# 7688A.net
KiCad netlist of a schematic drawn in Altium Designer
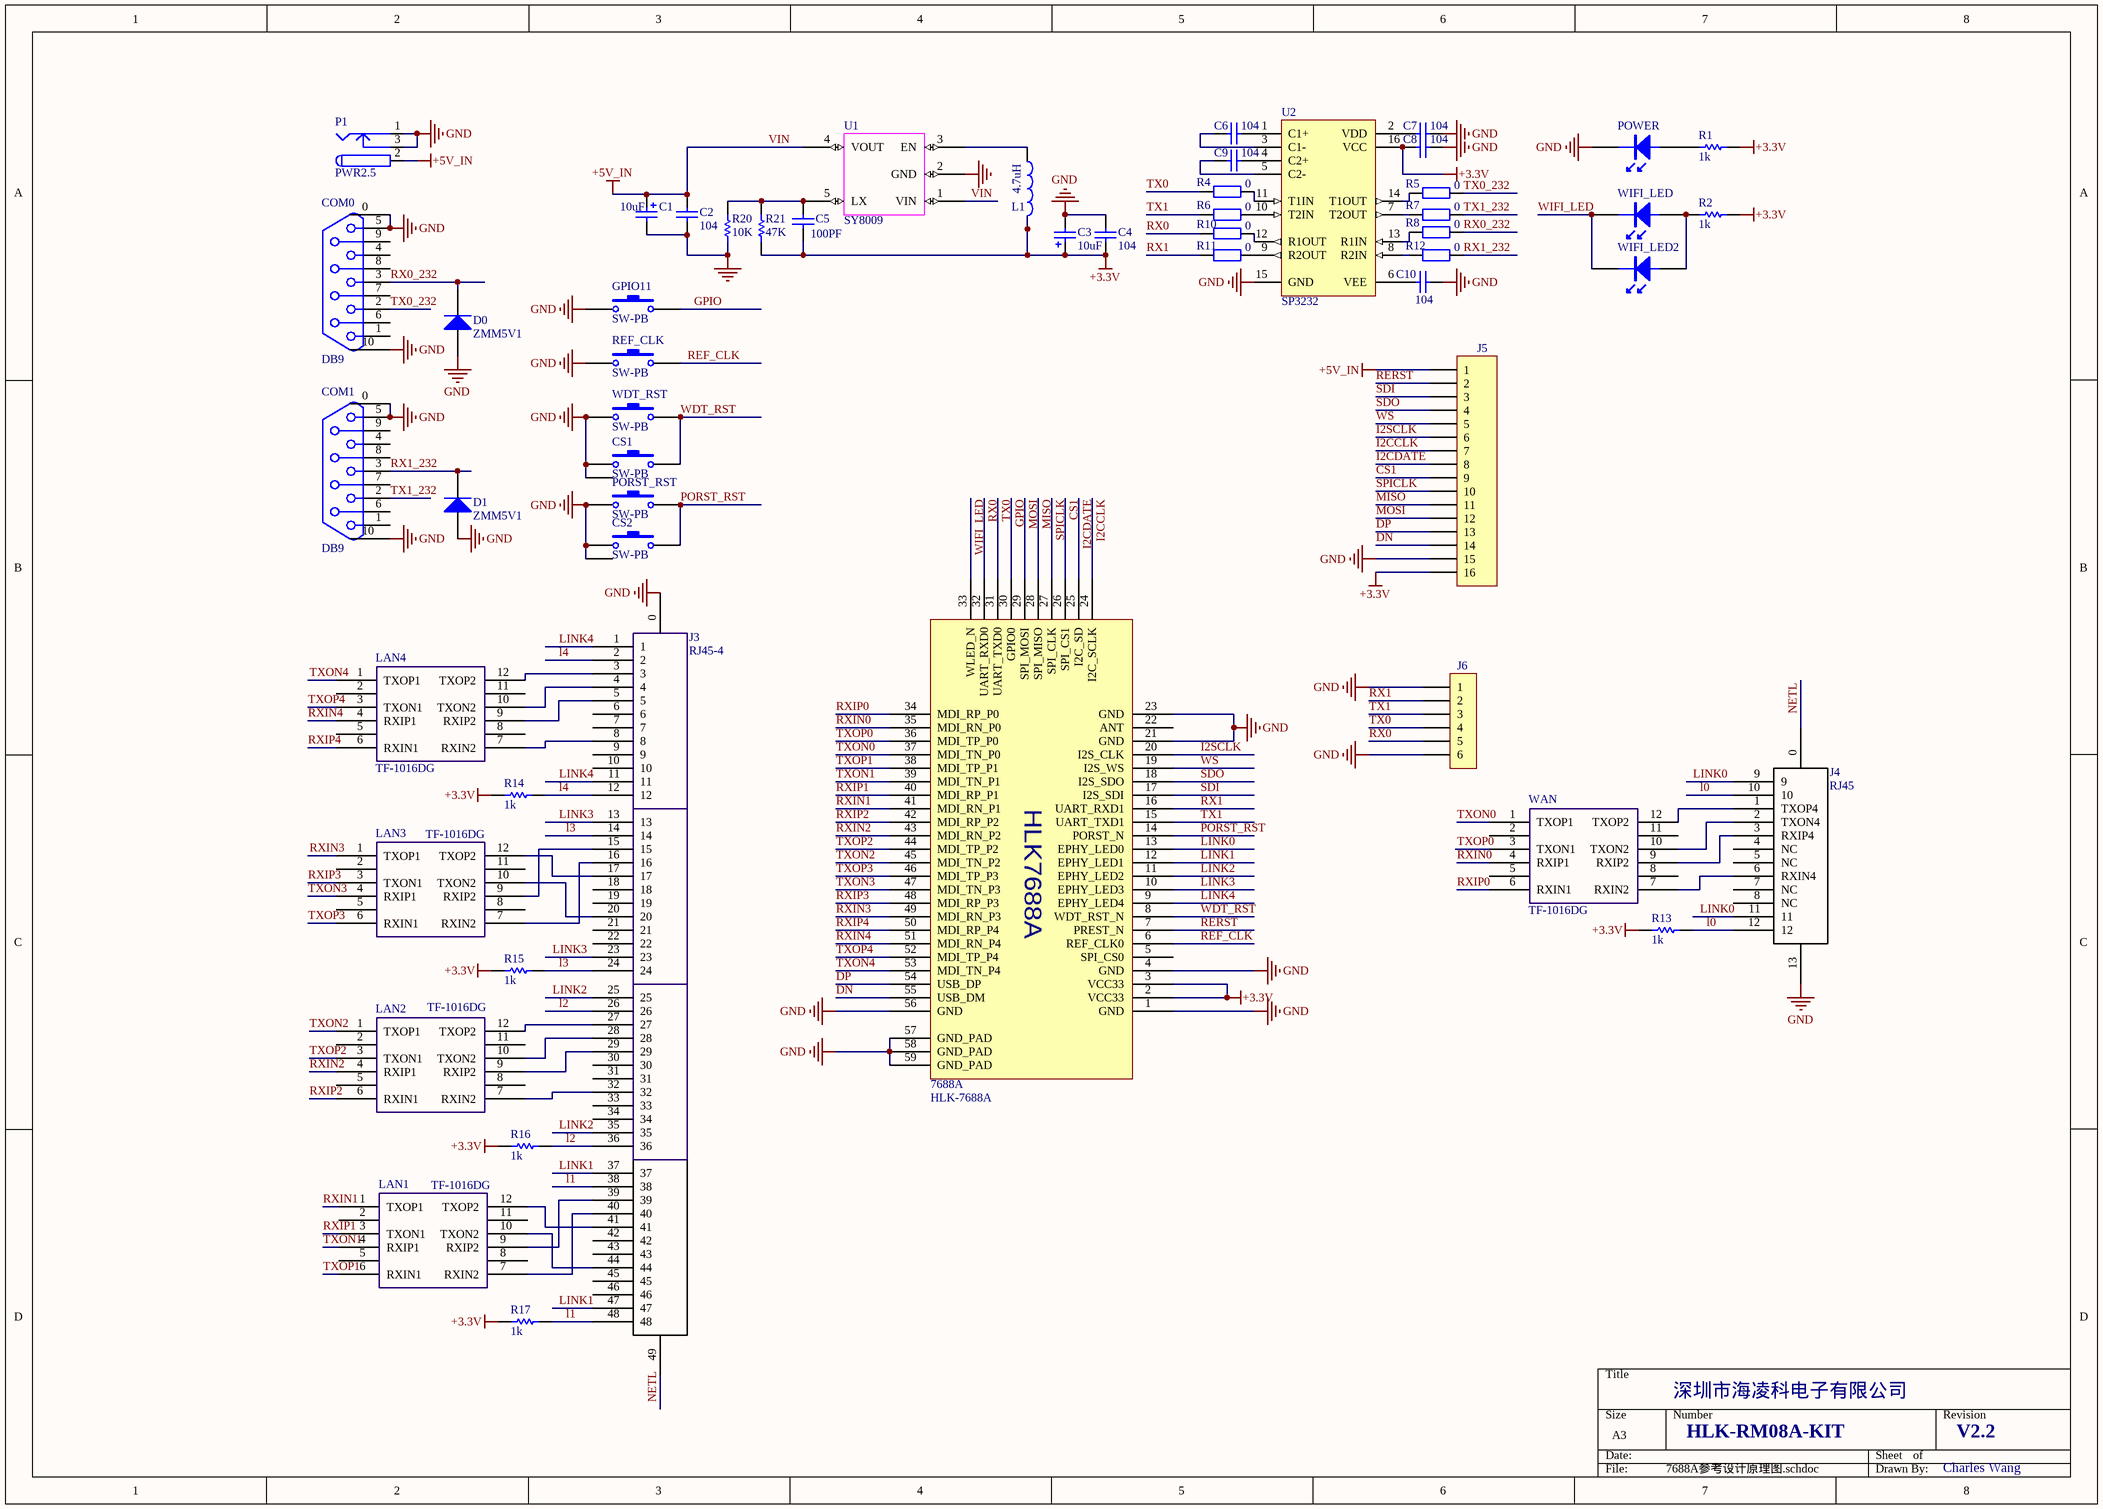
[diagram p0: 7688A参考设计原理图.schdoc]

(export (version "E")
  (design (tool "Eeschema 10.0.6"))
  (components
    (comp (ref "7688A")
      (value "HLK-7688A")
      (footprint "7688A_59pin:7688A")
      (libsource (lib "7688A原理图封装") (part "Component_1"))
    )
    (comp (ref "C1")
      (value "10uF")
      (footprint "0805")
      (description "Polarized Capacitor (Surface Mount)")
      (fields
        (field (name "MANUFACTURER") "Generic Components")
        (field (name "PUBLISHER") "Altium Hobart Technology Centre")
      )
      (libsource (lib "*") (part "Cap Pol3"))
    )
    (comp (ref "C2")
      (value "104")
      (footprint "0603L")
      (description "Capacitor")
      (fields
        (field (name "MANUFACTURER") "Generic Components")
        (field (name "PUBLISHER") "Altium Hobart Technology Centre")
      )
      (libsource (lib "*") (part "Cap"))
    )
    (comp (ref "C3")
      (value "10uF")
      (footprint "0805")
      (description "Polarized Capacitor (Surface Mount)")
      (fields
        (field (name "MANUFACTURER") "Generic Components")
        (field (name "PUBLISHER") "Altium Hobart Technology Centre")
      )
      (libsource (lib "*") (part "Cap Pol3"))
    )
    (comp (ref "C4")
      (value "104")
      (footprint "0603L")
      (description "Capacitor")
      (fields
        (field (name "MANUFACTURER") "Generic Components")
        (field (name "PUBLISHER") "Altium Hobart Technology Centre")
      )
      (libsource (lib "*") (part "Cap"))
    )
    (comp (ref "C5")
      (value "100PF")
      (footprint "0603L")
      (description "Capacitor")
      (fields
        (field (name "MANUFACTURER") "Generic Components")
        (field (name "PUBLISHER") "Altium Hobart Technology Centre")
      )
      (libsource (lib "*") (part "Cap"))
    )
    (comp (ref "C6")
      (value "104")
      (footprint "0603")
      (description "Capacitor")
      (fields (field (name "PUBLISHER") "Altium Limited"))
      (libsource (lib "HLK-RM04_KIT-V2.3") (part "Cap"))
    )
    (comp (ref "C7")
      (value "104")
      (footprint "0603")
      (description "Capacitor")
      (fields (field (name "PUBLISHER") "Altium Limited"))
      (libsource (lib "HLK-RM04_KIT-V2.3") (part "Cap"))
    )
    (comp (ref "C8")
      (value "104")
      (footprint "0603")
      (description "Capacitor")
      (fields (field (name "PUBLISHER") "Altium Limited"))
      (libsource (lib "HLK-RM04_KIT-V2.3") (part "Cap"))
    )
    (comp (ref "C9")
      (value "104")
      (footprint "0603")
      (description "Capacitor")
      (fields (field (name "PUBLISHER") "Altium Limited"))
      (libsource (lib "HLK-RM04_KIT-V2.3") (part "Cap"))
    )
    (comp (ref "C10")
      (value "104")
      (footprint "0603")
      (description "Capacitor")
      (fields (field (name "PUBLISHER") "Altium Limited"))
      (libsource (lib "HLK-RM04_KIT-V2.3") (part "Cap"))
    )
    (comp (ref "COM0") (value "DB9") (footprint "DB9s") (libsource (lib "Schlib1") (part "DB9")))
    (comp (ref "COM1") (value "DB9") (footprint "DB9s") (libsource (lib "Schlib1") (part "DB9")))
    (comp (ref "CS1")
      (value "SW-PB")
      (footprint "K5")
      (description "Switch")
      (fields (field (name "PUBLISHER") "Altium Limited"))
      (libsource (lib "") (part "SW-PB_1"))
    )
    (comp (ref "CS2")
      (value "SW-PB")
      (footprint "K5")
      (description "Switch")
      (fields (field (name "PUBLISHER") "Altium Limited"))
      (libsource (lib "") (part "SW-PB_1"))
    )
    (comp (ref "D0")
      (value "ZMM5V1")
      (footprint "1005D")
      (description "Default Diode")
      (fields (field (name "PUBLISHER") "Altium Limited"))
      (libsource (lib "Miscellaneous Devices") (part "Diode"))
    )
    (comp (ref "D1")
      (value "ZMM5V1")
      (footprint "1005D")
      (description "Default Diode")
      (fields (field (name "PUBLISHER") "Altium Limited"))
      (libsource (lib "Miscellaneous Devices") (part "Diode"))
    )
    (comp (ref "GPIO11")
      (value "SW-PB")
      (footprint "SWITCH")
      (description "Switch")
      (fields (field (name "PUBLISHER") "Altium Limited"))
      (libsource (lib "Miscellaneous Devices") (part "SW-PB"))
    )
    (comp (ref "J3") (value "RJ45-4") (footprint "RJ45-4-LED") (libsource (lib "Schlib1") (part "RJ45-4")))
    (comp (ref "J4") (value "RJ45") (libsource (lib "Schlib1") (part "RJ45_1")))
    (comp (ref "J5")
      (value "2.54*16")
      (footprint "HDR1X16")
      (description "Connector")
      (libsource (lib "Miscellaneous Devices") (part "CON16"))
    )
    (comp (ref "J6")
      (value "2.54*6")
      (description "Connector")
      (libsource (lib "Miscellaneous Devices") (part "CON6"))
    )
    (comp (ref "L1") (value "4.7uH") (footprint "L322520") (libsource (lib "ARM9") (part "INDUCTOR1")))
    (comp (ref "LAN1")
      (value "TF-1016DG")
      (footprint "tf-1016dg")
      (libsource (lib "TF-1016DG") (part "Component_1"))
    )
    (comp (ref "LAN2")
      (value "TF-1016DG")
      (footprint "tf-1016dg")
      (libsource (lib "TF-1016DG") (part "Component_1"))
    )
    (comp (ref "LAN3")
      (value "TF-1016DG")
      (footprint "tf-1016dg")
      (libsource (lib "TF-1016DG") (part "Component_1"))
    )
    (comp (ref "LAN4")
      (value "TF-1016DG")
      (footprint "tf-1016dg")
      (libsource (lib "TF-1016DG") (part "Component_1"))
    )
    (comp (ref "P1")
      (value "PWR2.5")
      (footprint "HLK-M35-KIT-V2.1:POWER_STK1")
      (description "Low Voltage Power Supply Connector")
      (libsource (lib "HLK-RM04_KIT-V2.3") (part "PWR2.5"))
    )
    (comp (ref "PORST_RST")
      (value "SW-PB")
      (footprint "SWITCH")
      (description "Switch")
      (fields (field (name "PUBLISHER") "Altium Limited"))
      (libsource (lib "Miscellaneous Devices") (part "SW-PB"))
    )
    (comp (ref "POWER")
      (value "~")
      (footprint "0603LED")
      (libsource (lib "Miscellaneous Devices") (part "LED"))
    )
    (comp (ref "R1")
      (value "1k")
      (footprint "0603")
      (description "Resistor")
      (fields (field (name "Comment") "Res1") (field (name "PUBLISHER") "Altium Limited"))
      (libsource (lib "Miscellaneous Devices") (part "Res1"))
    )
    (comp (ref "R2")
      (value "1k")
      (footprint "0603")
      (description "Resistor")
      (fields (field (name "Comment") "Res1") (field (name "PUBLISHER") "Altium Limited"))
      (libsource (lib "Miscellaneous Devices") (part "Res1"))
    )
    (comp (ref "R4")
      (value "0")
      (footprint "0603")
      (description "Resistor")
      (fields (field (name "PUBLISHER") "Altium Limited"))
      (libsource (lib "HLK-RM04_KIT-V2.3") (part "Res2"))
    )
    (comp (ref "R5")
      (value "0")
      (footprint "0603")
      (description "Resistor")
      (fields (field (name "PUBLISHER") "Altium Limited"))
      (libsource (lib "HLK-RM04_KIT-V2.3") (part "Res2"))
    )
    (comp (ref "R6")
      (value "0")
      (footprint "0603")
      (description "Resistor")
      (fields (field (name "PUBLISHER") "Altium Limited"))
      (libsource (lib "HLK-RM04_KIT-V2.3") (part "Res2"))
    )
    (comp (ref "R7")
      (value "0")
      (footprint "0603")
      (description "Resistor")
      (fields (field (name "PUBLISHER") "Altium Limited"))
      (libsource (lib "HLK-RM04_KIT-V2.3") (part "Res2"))
    )
    (comp (ref "R8")
      (value "0")
      (footprint "0603")
      (description "Resistor")
      (fields (field (name "PUBLISHER") "Altium Limited"))
      (libsource (lib "HLK-RM04_KIT-V2.3") (part "Res2"))
    )
    (comp (ref "R10")
      (value "0")
      (footprint "0603")
      (description "Resistor")
      (fields (field (name "PUBLISHER") "Altium Limited"))
      (libsource (lib "HLK-RM04_KIT-V2.3") (part "Res2"))
    )
    (comp (ref "R11")
      (value "0")
      (footprint "0603")
      (description "Resistor")
      (fields (field (name "PUBLISHER") "Altium Limited"))
      (libsource (lib "HLK-RM04_KIT-V2.3") (part "Res2"))
    )
    (comp (ref "R12")
      (value "0")
      (footprint "0603")
      (description "Resistor")
      (fields (field (name "PUBLISHER") "Altium Limited"))
      (libsource (lib "HLK-RM04_KIT-V2.3") (part "Res2"))
    )
    (comp (ref "R13")
      (value "1k")
      (footprint "0603")
      (description "Resistor")
      (fields (field (name "Comment") "Res1") (field (name "PUBLISHER") "Altium Limited"))
      (libsource (lib "Miscellaneous Devices") (part "Res1"))
    )
    (comp (ref "R14")
      (value "1k")
      (footprint "0603")
      (description "Resistor")
      (fields (field (name "Comment") "Res1") (field (name "PUBLISHER") "Altium Limited"))
      (libsource (lib "Miscellaneous Devices") (part "Res1"))
    )
    (comp (ref "R15")
      (value "1k")
      (footprint "0603")
      (description "Resistor")
      (fields (field (name "Comment") "Res1") (field (name "PUBLISHER") "Altium Limited"))
      (libsource (lib "Miscellaneous Devices") (part "Res1"))
    )
    (comp (ref "R16")
      (value "1k")
      (footprint "0603")
      (description "Resistor")
      (fields (field (name "Comment") "Res1") (field (name "PUBLISHER") "Altium Limited"))
      (libsource (lib "Miscellaneous Devices") (part "Res1"))
    )
    (comp (ref "R17")
      (value "1k")
      (footprint "0603")
      (description "Resistor")
      (fields (field (name "Comment") "Res1") (field (name "PUBLISHER") "Altium Limited"))
      (libsource (lib "Miscellaneous Devices") (part "Res1"))
    )
    (comp (ref "R20")
      (value "10K")
      (footprint "0603L")
      (description "Resistor")
      (fields (field (name "Comment") "Res1") (field (name "PUBLISHER") "Altium Limited"))
      (libsource (lib "Miscellaneous Devices") (part "Res1"))
    )
    (comp (ref "R21")
      (value "47K")
      (footprint "0603L")
      (description "Resistor")
      (fields (field (name "Comment") "Res1") (field (name "PUBLISHER") "Altium Limited"))
      (libsource (lib "Miscellaneous Devices") (part "Res1"))
    )
    (comp (ref "REF_CLK")
      (value "SW-PB")
      (footprint "SWITCH")
      (description "Switch")
      (fields (field (name "PUBLISHER") "Altium Limited"))
      (libsource (lib "Miscellaneous Devices") (part "SW-PB"))
    )
    (comp (ref "U1") (value "SY8009") (footprint "SOT-25") (libsource (lib "ARM9") (part "RT8009")))
    (comp (ref "U2")
      (value "SP3232")
      (footprint "HLK-M35-KIT-V2.1:MAX3232")
      (description "+5V Powered, Multi-Channel RS-232 Driver/Receiver")
      (fields (field (name "PUBLISHER") "Altium Limited"))
      (libsource (lib "HLK-RM04_KIT-V2.3") (part "MAX232ACPE"))
    )
    (comp (ref "WAN")
      (value "TF-1016DG")
      (footprint "tf-1016dg")
      (libsource (lib "TF-1016DG") (part "Component_1"))
    )
    (comp (ref "WDT_RST")
      (value "SW-PB")
      (footprint "SWITCH")
      (description "Switch")
      (fields (field (name "PUBLISHER") "Altium Limited"))
      (libsource (lib "Miscellaneous Devices") (part "SW-PB"))
    )
    (comp (ref "WIFI_LED")
      (value "~")
      (footprint "0603LED")
      (libsource (lib "Miscellaneous Devices") (part "LED"))
    )
    (comp (ref "WIFI_LED2")
      (value "~")
      (footprint "LED0.2")
      (libsource (lib "Miscellaneous Devices") (part "LED"))
    )
  )
  (nets
    (net (code "1") (name "+3.3V") (class "Default")
      (node (ref "7688A") (pin "2") (pinfunction "VCC33_2") (pintype "passive"))
      (node (ref "7688A") (pin "3") (pinfunction "VCC33_3") (pintype "passive"))
      (node (ref "C3") (pin "1") (pinfunction "1_1") (pintype "passive"))
      (node (ref "C4") (pin "1") (pinfunction "1_1") (pintype "passive"))
      (node (ref "C5") (pin "1") (pinfunction "1_1") (pintype "passive"))
      (node (ref "C8") (pin "1") (pinfunction "1_1") (pintype "passive"))
      (node (ref "J5") (pin "16") (pinfunction "16_16") (pintype "passive"))
      (node (ref "L1") (pin "2") (pinfunction "2_2") (pintype "passive"))
      (node (ref "R1") (pin "2") (pinfunction "2_2") (pintype "passive"))
      (node (ref "R13") (pin "2") (pinfunction "2_2") (pintype "passive"))
      (node (ref "R14") (pin "2") (pinfunction "2_2") (pintype "passive"))
      (node (ref "R15") (pin "2") (pinfunction "2_2") (pintype "passive"))
      (node (ref "R16") (pin "2") (pinfunction "2_2") (pintype "passive"))
      (node (ref "R17") (pin "2") (pinfunction "2_2") (pintype "passive"))
      (node (ref "R2") (pin "2") (pinfunction "2_2") (pintype "passive"))
      (node (ref "R21") (pin "2") (pinfunction "2_2") (pintype "passive"))
      (node (ref "U2") (pin "16") (pinfunction "VCC_16") (pintype "power_in"))
    )
    (net (code "2") (name "+5V_IN") (class "Default")
      (node (ref "C1") (pin "1") (pinfunction "1_1") (pintype "passive"))
      (node (ref "C2") (pin "1") (pinfunction "1_1") (pintype "passive"))
      (node (ref "J5") (pin "1") (pinfunction "1_1") (pintype "passive"))
      (node (ref "P1") (pin "2") (pinfunction "2_2") (pintype "power_in"))
      (node (ref "U1") (pin "1") (pinfunction "VIN_1") (pintype "bidirectional"))
      (node (ref "U1") (pin "4") (pinfunction "VOUT_4") (pintype "bidirectional"))
    )
    (net (code "3") (name "/CS1") (class "Default")
      (node (ref "7688A") (pin "26") (pinfunction "SPI_CS1_26") (pintype "passive"))
      (node (ref "J5") (pin "9") (pinfunction "9_9") (pintype "passive"))
    )
    (net (code "4") (name "/DN") (class "Default")
      (node (ref "7688A") (pin "55") (pinfunction "USB_DM_55") (pintype "passive"))
      (node (ref "J5") (pin "14") (pinfunction "14_14") (pintype "passive"))
    )
    (net (code "5") (name "/DP") (class "Default")
      (node (ref "7688A") (pin "54") (pinfunction "USB_DP_54") (pintype "passive"))
      (node (ref "J5") (pin "13") (pinfunction "13_13") (pintype "passive"))
    )
    (net (code "6") (name "/GPIO") (class "Default")
      (node (ref "7688A") (pin "30") (pinfunction "GPIO0_30") (pintype "passive"))
      (node (ref "GPIO11") (pin "2") (pinfunction "2_2") (pintype "passive"))
    )
    (net (code "7") (name "/I2CCLK") (class "Default")
      (node (ref "7688A") (pin "24") (pinfunction "I2C_SCLK_24") (pintype "passive"))
      (node (ref "J5") (pin "7") (pinfunction "7_7") (pintype "passive"))
    )
    (net (code "8") (name "/I2CDATE") (class "Default")
      (node (ref "7688A") (pin "25") (pinfunction "I2C_SD_25") (pintype "passive"))
      (node (ref "J5") (pin "8") (pinfunction "8_8") (pintype "passive"))
    )
    (net (code "9") (name "/I2SCLK") (class "Default")
      (node (ref "7688A") (pin "20") (pinfunction "I2S_CLK_20") (pintype "passive"))
      (node (ref "J5") (pin "6") (pinfunction "6_6") (pintype "passive"))
    )
    (net (code "10") (name "/LINK0") (class "Default")
      (node (ref "7688A") (pin "13") (pinfunction "EPHY_LED0_13") (pintype "passive"))
      (node (ref "J4") (pin "11") (pinfunction "11_11") (pintype "passive"))
      (node (ref "J4") (pin "9") (pinfunction "9_9") (pintype "passive"))
    )
    (net (code "11") (name "/LINK1") (class "Default")
      (node (ref "7688A") (pin "12") (pinfunction "EPHY_LED1_12") (pintype "passive"))
      (node (ref "J3") (pin "37") (pinfunction "37_37") (pintype "passive"))
      (node (ref "J3") (pin "47") (pinfunction "47_47") (pintype "passive"))
    )
    (net (code "12") (name "/LINK2") (class "Default")
      (node (ref "7688A") (pin "11") (pinfunction "EPHY_LED2_11") (pintype "passive"))
      (node (ref "J3") (pin "25") (pinfunction "25_25") (pintype "passive"))
      (node (ref "J3") (pin "35") (pinfunction "35_35") (pintype "passive"))
    )
    (net (code "13") (name "/LINK3") (class "Default")
      (node (ref "7688A") (pin "10") (pinfunction "EPHY_LED3_10") (pintype "passive"))
      (node (ref "J3") (pin "13") (pinfunction "13_13") (pintype "passive"))
      (node (ref "J3") (pin "23") (pinfunction "23_23") (pintype "passive"))
    )
    (net (code "14") (name "/LINK4") (class "Default")
      (node (ref "7688A") (pin "9") (pinfunction "EPHY_LED4_9") (pintype "passive"))
      (node (ref "J3") (pin "1") (pinfunction "1_1") (pintype "passive"))
      (node (ref "J3") (pin "11") (pinfunction "11_11") (pintype "passive"))
    )
    (net (code "15") (name "/MISO") (class "Default")
      (node (ref "7688A") (pin "28") (pinfunction "SPI_MISO_28") (pintype "passive"))
      (node (ref "J5") (pin "11") (pinfunction "11_11") (pintype "passive"))
    )
    (net (code "16") (name "/MOSI") (class "Default")
      (node (ref "7688A") (pin "29") (pinfunction "SPI_MOSI_29") (pintype "passive"))
      (node (ref "J5") (pin "12") (pinfunction "12_12") (pintype "passive"))
    )
    (net (code "17") (name "/NETL") (class "Default")
      (node (ref "J3") (pin "49") (pinfunction "49_49") (pintype "passive"))
      (node (ref "J4") (pin "0") (pinfunction "0_0") (pintype "passive"))
    )
    (net (code "18") (name "/PORST_RST") (class "Default")
      (node (ref "7688A") (pin "14") (pinfunction "PORST_N_14") (pintype "passive"))
      (node (ref "CS2") (pin "2") (pinfunction "2_2") (pintype "passive"))
      (node (ref "PORST_RST") (pin "2") (pinfunction "2_2") (pintype "passive"))
    )
    (net (code "19") (name "/REF_CLK") (class "Default")
      (node (ref "7688A") (pin "6") (pinfunction "REF_CLK0_6") (pintype "passive"))
      (node (ref "REF_CLK") (pin "2") (pinfunction "2_2") (pintype "passive"))
    )
    (net (code "20") (name "/RERST") (class "Default")
      (node (ref "7688A") (pin "7") (pinfunction "PREST_N_7") (pintype "passive"))
      (node (ref "J5") (pin "2") (pinfunction "2_2") (pintype "passive"))
    )
    (net (code "21") (name "/RX0") (class "Default")
      (node (ref "7688A") (pin "32") (pinfunction "UART_RXD0_32") (pintype "passive"))
      (node (ref "J6") (pin "5") (pinfunction "5_5") (pintype "passive"))
      (node (ref "R10") (pin "1") (pinfunction "1_1") (pintype "passive"))
    )
    (net (code "22") (name "/RX0_232") (class "Default")
      (node (ref "COM0") (pin "3") (pinfunction "3_3") (pintype "passive"))
      (node (ref "D0") (pin "2") (pinfunction "K_2") (pintype "passive"))
      (node (ref "R8") (pin "2") (pinfunction "2_2") (pintype "passive"))
    )
    (net (code "23") (name "/RX1") (class "Default")
      (node (ref "7688A") (pin "16") (pinfunction "UART_RXD1_16") (pintype "passive"))
      (node (ref "J6") (pin "2") (pinfunction "2_2") (pintype "passive"))
      (node (ref "R11") (pin "1") (pinfunction "1_1") (pintype "passive"))
    )
    (net (code "24") (name "/RX1_232") (class "Default")
      (node (ref "COM1") (pin "3") (pinfunction "3_3") (pintype "passive"))
      (node (ref "D1") (pin "2") (pinfunction "K_2") (pintype "passive"))
      (node (ref "R12") (pin "2") (pinfunction "2_2") (pintype "passive"))
    )
    (net (code "25") (name "/RXIN0") (class "Default")
      (node (ref "7688A") (pin "35") (pinfunction "MDI_RN_P0_35") (pintype "passive"))
      (node (ref "WAN") (pin "4") (pinfunction "RXIP1_4") (pintype "passive"))
    )
    (net (code "26") (name "/RXIN1") (class "Default")
      (node (ref "7688A") (pin "41") (pinfunction "MDI_RN_P1_41") (pintype "passive"))
      (node (ref "LAN1") (pin "1") (pinfunction "TXOP1_1") (pintype "passive"))
    )
    (net (code "27") (name "/RXIN2") (class "Default")
      (node (ref "7688A") (pin "43") (pinfunction "MDI_RN_P2_43") (pintype "passive"))
      (node (ref "LAN2") (pin "4") (pinfunction "RXIP1_4") (pintype "passive"))
    )
    (net (code "28") (name "/RXIN3") (class "Default")
      (node (ref "7688A") (pin "49") (pinfunction "MDI_RN_P3_49") (pintype "passive"))
      (node (ref "LAN3") (pin "1") (pinfunction "TXOP1_1") (pintype "passive"))
    )
    (net (code "29") (name "/RXIN4") (class "Default")
      (node (ref "7688A") (pin "51") (pinfunction "MDI_RN_P4_51") (pintype "passive"))
      (node (ref "LAN4") (pin "4") (pinfunction "RXIP1_4") (pintype "passive"))
    )
    (net (code "30") (name "/RXIP0") (class "Default")
      (node (ref "7688A") (pin "34") (pinfunction "MDI_RP_P0_34") (pintype "passive"))
      (node (ref "WAN") (pin "6") (pinfunction "RXIN1_6") (pintype "passive"))
    )
    (net (code "31") (name "/RXIP1") (class "Default")
      (node (ref "7688A") (pin "40") (pinfunction "MDI_RP_P1_40") (pintype "passive"))
      (node (ref "LAN1") (pin "3") (pinfunction "TXON1_3") (pintype "passive"))
    )
    (net (code "32") (name "/RXIP2") (class "Default")
      (node (ref "7688A") (pin "42") (pinfunction "MDI_RP_P2_42") (pintype "passive"))
      (node (ref "LAN2") (pin "6") (pinfunction "RXIN1_6") (pintype "passive"))
    )
    (net (code "33") (name "/RXIP3") (class "Default")
      (node (ref "7688A") (pin "48") (pinfunction "MDI_RP_P3_48") (pintype "passive"))
      (node (ref "LAN3") (pin "3") (pinfunction "TXON1_3") (pintype "passive"))
    )
    (net (code "34") (name "/RXIP4") (class "Default")
      (node (ref "7688A") (pin "50") (pinfunction "MDI_RP_P4_50") (pintype "passive"))
      (node (ref "LAN4") (pin "6") (pinfunction "RXIN1_6") (pintype "passive"))
    )
    (net (code "35") (name "/SDI") (class "Default")
      (node (ref "7688A") (pin "17") (pinfunction "I2S_SDI_17") (pintype "passive"))
      (node (ref "J5") (pin "3") (pinfunction "3_3") (pintype "passive"))
    )
    (net (code "36") (name "/SDO") (class "Default")
      (node (ref "7688A") (pin "18") (pinfunction "I2S_SDO_18") (pintype "passive"))
      (node (ref "J5") (pin "4") (pinfunction "4_4") (pintype "passive"))
    )
    (net (code "37") (name "/SPICLK") (class "Default")
      (node (ref "7688A") (pin "27") (pinfunction "SPI_CLK_27") (pintype "passive"))
      (node (ref "J5") (pin "10") (pinfunction "10_10") (pintype "passive"))
    )
    (net (code "38") (name "/TX0") (class "Default")
      (node (ref "7688A") (pin "31") (pinfunction "UART_TXD0_31") (pintype "passive"))
      (node (ref "J6") (pin "4") (pinfunction "4_4") (pintype "passive"))
      (node (ref "R4") (pin "1") (pinfunction "1_1") (pintype "passive"))
    )
    (net (code "39") (name "/TX0_232") (class "Default")
      (node (ref "COM0") (pin "2") (pinfunction "2_2") (pintype "passive"))
      (node (ref "R5") (pin "2") (pinfunction "2_2") (pintype "passive"))
    )
    (net (code "40") (name "/TX1") (class "Default")
      (node (ref "7688A") (pin "15") (pinfunction "UART_TXD1_15") (pintype "passive"))
      (node (ref "J6") (pin "3") (pinfunction "3_3") (pintype "passive"))
      (node (ref "R6") (pin "1") (pinfunction "1_1") (pintype "passive"))
    )
    (net (code "41") (name "/TX1_232") (class "Default")
      (node (ref "COM1") (pin "2") (pinfunction "2_2") (pintype "passive"))
      (node (ref "R7") (pin "2") (pinfunction "2_2") (pintype "passive"))
    )
    (net (code "42") (name "/TXON0") (class "Default")
      (node (ref "7688A") (pin "37") (pinfunction "MDI_TN_P0_37") (pintype "passive"))
      (node (ref "WAN") (pin "1") (pinfunction "TXOP1_1") (pintype "passive"))
    )
    (net (code "43") (name "/TXON1") (class "Default")
      (node (ref "7688A") (pin "39") (pinfunction "MDI_TN_P1_39") (pintype "passive"))
      (node (ref "LAN1") (pin "4") (pinfunction "RXIP1_4") (pintype "passive"))
    )
    (net (code "44") (name "/TXON2") (class "Default")
      (node (ref "7688A") (pin "45") (pinfunction "MDI_TN_P2_45") (pintype "passive"))
      (node (ref "LAN2") (pin "1") (pinfunction "TXOP1_1") (pintype "passive"))
    )
    (net (code "45") (name "/TXON3") (class "Default")
      (node (ref "7688A") (pin "47") (pinfunction "MDI_TN_P3_47") (pintype "passive"))
      (node (ref "LAN3") (pin "4") (pinfunction "RXIP1_4") (pintype "passive"))
    )
    (net (code "46") (name "/TXON4") (class "Default")
      (node (ref "7688A") (pin "53") (pinfunction "MDI_TN_P4_53") (pintype "passive"))
      (node (ref "LAN4") (pin "1") (pinfunction "TXOP1_1") (pintype "passive"))
    )
    (net (code "47") (name "/TXOP0") (class "Default")
      (node (ref "7688A") (pin "36") (pinfunction "MDI_TP_P0_36") (pintype "passive"))
      (node (ref "WAN") (pin "3") (pinfunction "TXON1_3") (pintype "passive"))
    )
    (net (code "48") (name "/TXOP1") (class "Default")
      (node (ref "7688A") (pin "38") (pinfunction "MDI_TP_P1_38") (pintype "passive"))
      (node (ref "LAN1") (pin "6") (pinfunction "RXIN1_6") (pintype "passive"))
    )
    (net (code "49") (name "/TXOP2") (class "Default")
      (node (ref "7688A") (pin "44") (pinfunction "MDI_TP_P2_44") (pintype "passive"))
      (node (ref "LAN2") (pin "3") (pinfunction "TXON1_3") (pintype "passive"))
    )
    (net (code "50") (name "/TXOP3") (class "Default")
      (node (ref "7688A") (pin "46") (pinfunction "MDI_TP_P3_46") (pintype "passive"))
      (node (ref "LAN3") (pin "6") (pinfunction "RXIN1_6") (pintype "passive"))
    )
    (net (code "51") (name "/TXOP4") (class "Default")
      (node (ref "7688A") (pin "52") (pinfunction "MDI_TP_P4_52") (pintype "passive"))
      (node (ref "LAN4") (pin "3") (pinfunction "TXON1_3") (pintype "passive"))
    )
    (net (code "52") (name "/WDT_RST") (class "Default")
      (node (ref "7688A") (pin "8") (pinfunction "WDT_RST_N_8") (pintype "passive"))
      (node (ref "CS1") (pin "2") (pinfunction "2_2") (pintype "passive"))
      (node (ref "WDT_RST") (pin "2") (pinfunction "2_2") (pintype "passive"))
    )
    (net (code "53") (name "/WIFI_LED") (class "Default")
      (node (ref "7688A") (pin "33") (pinfunction "WLED_N_33") (pintype "passive"))
      (node (ref "WIFI_LED") (pin "2") (pinfunction "2_2") (pintype "passive"))
      (node (ref "WIFI_LED2") (pin "2") (pinfunction "2_2") (pintype "passive"))
    )
    (net (code "54") (name "/WS") (class "Default")
      (node (ref "7688A") (pin "19") (pinfunction "I2S_WS_19") (pintype "passive"))
      (node (ref "J5") (pin "5") (pinfunction "5_5") (pintype "passive"))
    )
    (net (code "55") (name "/l0") (class "Default")
      (node (ref "J4") (pin "10") (pinfunction "10_10") (pintype "passive"))
      (node (ref "J4") (pin "12") (pinfunction "12_12") (pintype "passive"))
      (node (ref "R13") (pin "1") (pinfunction "1_1") (pintype "passive"))
    )
    (net (code "56") (name "/l1") (class "Default")
      (node (ref "J3") (pin "38") (pinfunction "38_38") (pintype "passive"))
      (node (ref "J3") (pin "48") (pinfunction "48_48") (pintype "passive"))
      (node (ref "R17") (pin "1") (pinfunction "1_1") (pintype "passive"))
    )
    (net (code "57") (name "/l2") (class "Default")
      (node (ref "J3") (pin "26") (pinfunction "26_26") (pintype "passive"))
      (node (ref "J3") (pin "36") (pinfunction "36_36") (pintype "passive"))
      (node (ref "R16") (pin "1") (pinfunction "1_1") (pintype "passive"))
    )
    (net (code "58") (name "/l3") (class "Default")
      (node (ref "J3") (pin "14") (pinfunction "14_14") (pintype "passive"))
      (node (ref "J3") (pin "24") (pinfunction "24_24") (pintype "passive"))
      (node (ref "R15") (pin "1") (pinfunction "1_1") (pintype "passive"))
    )
    (net (code "59") (name "/l4") (class "Default")
      (node (ref "J3") (pin "12") (pinfunction "12_12") (pintype "passive"))
      (node (ref "J3") (pin "2") (pinfunction "2_2") (pintype "passive"))
      (node (ref "R14") (pin "1") (pinfunction "1_1") (pintype "passive"))
    )
    (net (code "60") (name "GND") (class "Default")
      (node (ref "7688A") (pin "1") (pinfunction "GND_1") (pintype "passive"))
      (node (ref "7688A") (pin "21") (pinfunction "GND_21") (pintype "passive"))
      (node (ref "7688A") (pin "23") (pinfunction "GND_23") (pintype "passive"))
      (node (ref "7688A") (pin "4") (pinfunction "GND_4") (pintype "passive"))
      (node (ref "7688A") (pin "56") (pinfunction "GND_56") (pintype "passive"))
      (node (ref "7688A") (pin "57") (pinfunction "GND_PAD_57") (pintype "passive"))
      (node (ref "7688A") (pin "58") (pinfunction "GND_PAD_58") (pintype "passive"))
      (node (ref "7688A") (pin "59") (pinfunction "GND_PAD_59") (pintype "passive"))
      (node (ref "C1") (pin "2") (pinfunction "2_2") (pintype "passive"))
      (node (ref "C10") (pin "1") (pinfunction "1_1") (pintype "passive"))
      (node (ref "C2") (pin "2") (pinfunction "2_2") (pintype "passive"))
      (node (ref "C3") (pin "2") (pinfunction "2_2") (pintype "passive"))
      (node (ref "C4") (pin "2") (pinfunction "2_2") (pintype "passive"))
      (node (ref "C7") (pin "2") (pinfunction "2_2") (pintype "passive"))
      (node (ref "C8") (pin "2") (pinfunction "2_2") (pintype "passive"))
      (node (ref "COM0") (pin "0") (pinfunction "0_0") (pintype "passive"))
      (node (ref "COM0") (pin "10") (pinfunction "10_10") (pintype "passive"))
      (node (ref "COM0") (pin "5") (pinfunction "5_5") (pintype "passive"))
      (node (ref "COM1") (pin "0") (pinfunction "0_0") (pintype "passive"))
      (node (ref "COM1") (pin "10") (pinfunction "10_10") (pintype "passive"))
      (node (ref "COM1") (pin "5") (pinfunction "5_5") (pintype "passive"))
      (node (ref "CS1") (pin "1") (pinfunction "1_1") (pintype "passive"))
      (node (ref "CS1") (pin "3") (pintype "passive"))
      (node (ref "CS2") (pin "1") (pinfunction "1_1") (pintype "passive"))
      (node (ref "CS2") (pin "3") (pintype "passive"))
      (node (ref "D0") (pin "1") (pinfunction "A_1") (pintype "passive"))
      (node (ref "D1") (pin "1") (pinfunction "A_1") (pintype "passive"))
      (node (ref "GPIO11") (pin "1") (pinfunction "1_1") (pintype "passive"))
      (node (ref "J3") (pin "0") (pinfunction "0_0") (pintype "passive"))
      (node (ref "J4") (pin "13") (pinfunction "13_13") (pintype "passive"))
      (node (ref "J5") (pin "15") (pinfunction "15_15") (pintype "passive"))
      (node (ref "J6") (pin "1") (pinfunction "1_1") (pintype "passive"))
      (node (ref "J6") (pin "6") (pinfunction "6_6") (pintype "passive"))
      (node (ref "P1") (pin "1") (pinfunction "1_1") (pintype "power_in"))
      (node (ref "P1") (pin "3") (pinfunction "3_3") (pintype "power_in"))
      (node (ref "PORST_RST") (pin "1") (pinfunction "1_1") (pintype "passive"))
      (node (ref "POWER") (pin "2") (pinfunction "2_2") (pintype "passive"))
      (node (ref "R20") (pin "1") (pinfunction "1_1") (pintype "passive"))
      (node (ref "REF_CLK") (pin "1") (pinfunction "1_1") (pintype "passive"))
      (node (ref "U1") (pin "2") (pinfunction "GND_2") (pintype "bidirectional"))
      (node (ref "U2") (pin "15") (pinfunction "GND_15") (pintype "power_in"))
      (node (ref "WDT_RST") (pin "1") (pinfunction "1_1") (pintype "passive"))
    )
    (net (code "61") (name "Net-(J4-RXIN4)") (class "Default")
      (node (ref "J4") (pin "6") (pinfunction "RXIN4_6") (pintype "passive"))
      (node (ref "WAN") (pin "7") (pinfunction "RXIN2_7") (pintype "passive"))
    )
    (net (code "62") (name "Net-(J4-RXIP4)") (class "Default")
      (node (ref "J4") (pin "3") (pinfunction "RXIP4_3") (pintype "passive"))
      (node (ref "WAN") (pin "9") (pinfunction "RXIP2_9") (pintype "passive"))
    )
    (net (code "63") (name "Net-(J4-TXON4)") (class "Default")
      (node (ref "J4") (pin "2") (pinfunction "TXON4_2") (pintype "passive"))
      (node (ref "WAN") (pin "10") (pinfunction "TXON2_10") (pintype "passive"))
    )
    (net (code "64") (name "Net-(J4-TXOP4)") (class "Default")
      (node (ref "J4") (pin "1") (pinfunction "TXOP4_1") (pintype "passive"))
      (node (ref "WAN") (pin "12") (pinfunction "TXOP2_12") (pintype "passive"))
    )
    (net (code "65") (name "Net-(LAN1-RXIN2)") (class "Default")
      (node (ref "J3") (pin "40") (pinfunction "40_40") (pintype "passive"))
      (node (ref "LAN1") (pin "7") (pinfunction "RXIN2_7") (pintype "passive"))
    )
    (net (code "66") (name "Net-(LAN1-RXIP2)") (class "Default")
      (node (ref "J3") (pin "39") (pinfunction "39_39") (pintype "passive"))
      (node (ref "LAN1") (pin "9") (pinfunction "RXIP2_9") (pintype "passive"))
    )
    (net (code "67") (name "Net-(LAN1-TXON2)") (class "Default")
      (node (ref "J3") (pin "44") (pinfunction "44_44") (pintype "passive"))
      (node (ref "LAN1") (pin "10") (pinfunction "TXON2_10") (pintype "passive"))
    )
    (net (code "68") (name "Net-(LAN1-TXOP2)") (class "Default")
      (node (ref "J3") (pin "41") (pinfunction "41_41") (pintype "passive"))
      (node (ref "LAN1") (pin "12") (pinfunction "TXOP2_12") (pintype "passive"))
    )
    (net (code "69") (name "Net-(LAN2-RXIN2)") (class "Default")
      (node (ref "J3") (pin "32") (pinfunction "32_32") (pintype "passive"))
      (node (ref "LAN2") (pin "7") (pinfunction "RXIN2_7") (pintype "passive"))
    )
    (net (code "70") (name "Net-(LAN2-RXIP2)") (class "Default")
      (node (ref "J3") (pin "29") (pinfunction "29_29") (pintype "passive"))
      (node (ref "LAN2") (pin "9") (pinfunction "RXIP2_9") (pintype "passive"))
    )
    (net (code "71") (name "Net-(LAN2-TXON2)") (class "Default")
      (node (ref "J3") (pin "28") (pinfunction "28_28") (pintype "passive"))
      (node (ref "LAN2") (pin "10") (pinfunction "TXON2_10") (pintype "passive"))
    )
    (net (code "72") (name "Net-(LAN2-TXOP2)") (class "Default")
      (node (ref "J3") (pin "27") (pinfunction "27_27") (pintype "passive"))
      (node (ref "LAN2") (pin "12") (pinfunction "TXOP2_12") (pintype "passive"))
    )
    (net (code "73") (name "Net-(LAN3-RXIN2)") (class "Default")
      (node (ref "J3") (pin "16") (pinfunction "16_16") (pintype "passive"))
      (node (ref "LAN3") (pin "7") (pinfunction "RXIN2_7") (pintype "passive"))
    )
    (net (code "74") (name "Net-(LAN3-RXIP2)") (class "Default")
      (node (ref "J3") (pin "15") (pinfunction "15_15") (pintype "passive"))
      (node (ref "LAN3") (pin "9") (pinfunction "RXIP2_9") (pintype "passive"))
    )
    (net (code "75") (name "Net-(LAN3-TXON2)") (class "Default")
      (node (ref "J3") (pin "20") (pinfunction "20_20") (pintype "passive"))
      (node (ref "LAN3") (pin "10") (pinfunction "TXON2_10") (pintype "passive"))
    )
    (net (code "76") (name "Net-(LAN3-TXOP2)") (class "Default")
      (node (ref "J3") (pin "17") (pinfunction "17_17") (pintype "passive"))
      (node (ref "LAN3") (pin "12") (pinfunction "TXOP2_12") (pintype "passive"))
    )
    (net (code "77") (name "Net-(LAN4-RXIN2)") (class "Default")
      (node (ref "J3") (pin "8") (pinfunction "8_8") (pintype "passive"))
      (node (ref "LAN4") (pin "7") (pinfunction "RXIN2_7") (pintype "passive"))
    )
    (net (code "78") (name "Net-(LAN4-RXIP2)") (class "Default")
      (node (ref "J3") (pin "5") (pinfunction "5_5") (pintype "passive"))
      (node (ref "LAN4") (pin "9") (pinfunction "RXIP2_9") (pintype "passive"))
    )
    (net (code "79") (name "Net-(LAN4-TXON2)") (class "Default")
      (node (ref "J3") (pin "4") (pinfunction "4_4") (pintype "passive"))
      (node (ref "LAN4") (pin "10") (pinfunction "TXON2_10") (pintype "passive"))
    )
    (net (code "80") (name "Net-(LAN4-TXOP2)") (class "Default")
      (node (ref "J3") (pin "3") (pinfunction "3_3") (pintype "passive"))
      (node (ref "LAN4") (pin "12") (pinfunction "TXOP2_12") (pintype "passive"))
    )
    (net (code "81") (name "Net-(POWER-Pad1)") (class "Default")
      (node (ref "POWER") (pin "1") (pinfunction "1_1") (pintype "passive"))
      (node (ref "R1") (pin "1") (pinfunction "1_1") (pintype "passive"))
    )
    (net (code "82") (name "Net-(R2-Pad1)") (class "Default")
      (node (ref "R2") (pin "1") (pinfunction "1_1") (pintype "passive"))
      (node (ref "WIFI_LED") (pin "1") (pinfunction "1_1") (pintype "passive"))
      (node (ref "WIFI_LED2") (pin "1") (pinfunction "1_1") (pintype "passive"))
    )
    (net (code "83") (name "Net-(U1-EN)") (class "Default")
      (node (ref "L1") (pin "1") (pinfunction "1_1") (pintype "passive"))
      (node (ref "U1") (pin "3") (pinfunction "EN_3") (pintype "bidirectional"))
    )
    (net (code "84") (name "Net-(U1-LX)") (class "Default")
      (node (ref "C5") (pin "2") (pinfunction "2_2") (pintype "passive"))
      (node (ref "R20") (pin "2") (pinfunction "2_2") (pintype "passive"))
      (node (ref "R21") (pin "1") (pinfunction "1_1") (pintype "passive"))
      (node (ref "U1") (pin "5") (pinfunction "LX_5") (pintype "bidirectional"))
    )
    (net (code "85") (name "Net-(U2-C1+)") (class "Default")
      (node (ref "C6") (pin "2") (pinfunction "2_2") (pintype "passive"))
      (node (ref "U2") (pin "1") (pinfunction "C1+_1") (pintype "passive"))
    )
    (net (code "86") (name "Net-(U2-C1-)") (class "Default")
      (node (ref "C6") (pin "1") (pinfunction "1_1") (pintype "passive"))
      (node (ref "U2") (pin "3") (pinfunction "C1-_3") (pintype "passive"))
    )
    (net (code "87") (name "Net-(U2-C2+)") (class "Default")
      (node (ref "C9") (pin "2") (pinfunction "2_2") (pintype "passive"))
      (node (ref "U2") (pin "4") (pinfunction "C2+_4") (pintype "passive"))
    )
    (net (code "88") (name "Net-(U2-C2-)") (class "Default")
      (node (ref "C9") (pin "1") (pinfunction "1_1") (pintype "passive"))
      (node (ref "U2") (pin "5") (pinfunction "C2-_5") (pintype "passive"))
    )
    (net (code "89") (name "Net-(U2-R1IN)") (class "Default")
      (node (ref "R8") (pin "1") (pinfunction "1_1") (pintype "passive"))
      (node (ref "U2") (pin "13") (pinfunction "R1IN_13") (pintype "input"))
    )
    (net (code "90") (name "Net-(U2-R1OUT)") (class "Default")
      (node (ref "R10") (pin "2") (pinfunction "2_2") (pintype "passive"))
      (node (ref "U2") (pin "12") (pinfunction "R1OUT_12") (pintype "output"))
    )
    (net (code "91") (name "Net-(U2-R2IN)") (class "Default")
      (node (ref "R12") (pin "1") (pinfunction "1_1") (pintype "passive"))
      (node (ref "U2") (pin "8") (pinfunction "R2IN_8") (pintype "input"))
    )
    (net (code "92") (name "Net-(U2-R2OUT)") (class "Default")
      (node (ref "R11") (pin "2") (pinfunction "2_2") (pintype "passive"))
      (node (ref "U2") (pin "9") (pinfunction "R2OUT_9") (pintype "output"))
    )
    (net (code "93") (name "Net-(U2-T1IN)") (class "Default")
      (node (ref "R4") (pin "2") (pinfunction "2_2") (pintype "passive"))
      (node (ref "U2") (pin "11") (pinfunction "T1IN_11") (pintype "input"))
    )
    (net (code "94") (name "Net-(U2-T1OUT)") (class "Default")
      (node (ref "R5") (pin "1") (pinfunction "1_1") (pintype "passive"))
      (node (ref "U2") (pin "14") (pinfunction "T1OUT_14") (pintype "output"))
    )
    (net (code "95") (name "Net-(U2-T2IN)") (class "Default")
      (node (ref "R6") (pin "2") (pinfunction "2_2") (pintype "passive"))
      (node (ref "U2") (pin "10") (pinfunction "T2IN_10") (pintype "input"))
    )
    (net (code "96") (name "Net-(U2-T2OUT)") (class "Default")
      (node (ref "R7") (pin "1") (pinfunction "1_1") (pintype "passive"))
      (node (ref "U2") (pin "7") (pinfunction "T2OUT_7") (pintype "output"))
    )
    (net (code "97") (name "Net-(U2-VDD)") (class "Default")
      (node (ref "C7") (pin "1") (pinfunction "1_1") (pintype "passive"))
      (node (ref "U2") (pin "2") (pinfunction "VDD_2") (pintype "power_in"))
    )
    (net (code "98") (name "Net-(U2-VEE)") (class "Default")
      (node (ref "C10") (pin "2") (pinfunction "2_2") (pintype "passive"))
      (node (ref "U2") (pin "6") (pinfunction "VEE_6") (pintype "power_in"))
    )
    (net (code "99") (name "unconnected-(7688A-ANT-Pad22)") (class "Default")
      (node (ref "7688A") (pin "22") (pinfunction "ANT_22") (pintype "passive"))
    )
    (net (code "100") (name "unconnected-(7688A-SPI_CS0-Pad5)") (class "Default")
      (node (ref "7688A") (pin "5") (pinfunction "SPI_CS0_5") (pintype "passive"))
    )
    (net (code "101") (name "unconnected-(COM0-Pad1)") (class "Default")
      (node (ref "COM0") (pin "1") (pinfunction "1_1") (pintype "passive"))
    )
    (net (code "102") (name "unconnected-(COM0-Pad4)") (class "Default")
      (node (ref "COM0") (pin "4") (pinfunction "4_4") (pintype "passive"))
    )
    (net (code "103") (name "unconnected-(COM0-Pad6)") (class "Default")
      (node (ref "COM0") (pin "6") (pinfunction "6_6") (pintype "passive"))
    )
    (net (code "104") (name "unconnected-(COM0-Pad7)") (class "Default")
      (node (ref "COM0") (pin "7") (pinfunction "7_7") (pintype "passive"))
    )
    (net (code "105") (name "unconnected-(COM0-Pad8)") (class "Default")
      (node (ref "COM0") (pin "8") (pinfunction "8_8") (pintype "passive"))
    )
    (net (code "106") (name "unconnected-(COM0-Pad9)") (class "Default")
      (node (ref "COM0") (pin "9") (pinfunction "9_9") (pintype "passive"))
    )
    (net (code "107") (name "unconnected-(COM1-Pad1)") (class "Default")
      (node (ref "COM1") (pin "1") (pinfunction "1_1") (pintype "passive"))
    )
    (net (code "108") (name "unconnected-(COM1-Pad4)") (class "Default")
      (node (ref "COM1") (pin "4") (pinfunction "4_4") (pintype "passive"))
    )
    (net (code "109") (name "unconnected-(COM1-Pad6)") (class "Default")
      (node (ref "COM1") (pin "6") (pinfunction "6_6") (pintype "passive"))
    )
    (net (code "110") (name "unconnected-(COM1-Pad7)") (class "Default")
      (node (ref "COM1") (pin "7") (pinfunction "7_7") (pintype "passive"))
    )
    (net (code "111") (name "unconnected-(COM1-Pad8)") (class "Default")
      (node (ref "COM1") (pin "8") (pinfunction "8_8") (pintype "passive"))
    )
    (net (code "112") (name "unconnected-(COM1-Pad9)") (class "Default")
      (node (ref "COM1") (pin "9") (pinfunction "9_9") (pintype "passive"))
    )
    (net (code "113") (name "unconnected-(J3-Pad6)") (class "Default")
      (node (ref "J3") (pin "6") (pinfunction "6_6") (pintype "passive"))
    )
    (net (code "114") (name "unconnected-(J3-Pad7)") (class "Default")
      (node (ref "J3") (pin "7") (pinfunction "7_7") (pintype "passive"))
    )
    (net (code "115") (name "unconnected-(J3-Pad9)") (class "Default")
      (node (ref "J3") (pin "9") (pinfunction "9_9") (pintype "passive"))
    )
    (net (code "116") (name "unconnected-(J3-Pad10)") (class "Default")
      (node (ref "J3") (pin "10") (pinfunction "10_10") (pintype "passive"))
    )
    (net (code "117") (name "unconnected-(J3-Pad18)") (class "Default")
      (node (ref "J3") (pin "18") (pinfunction "18_18") (pintype "passive"))
    )
    (net (code "118") (name "unconnected-(J3-Pad19)") (class "Default")
      (node (ref "J3") (pin "19") (pinfunction "19_19") (pintype "passive"))
    )
    (net (code "119") (name "unconnected-(J3-Pad21)") (class "Default")
      (node (ref "J3") (pin "21") (pinfunction "21_21") (pintype "passive"))
    )
    (net (code "120") (name "unconnected-(J3-Pad22)") (class "Default")
      (node (ref "J3") (pin "22") (pinfunction "22_22") (pintype "passive"))
    )
    (net (code "121") (name "unconnected-(J3-Pad30)") (class "Default")
      (node (ref "J3") (pin "30") (pinfunction "30_30") (pintype "passive"))
    )
    (net (code "122") (name "unconnected-(J3-Pad31)") (class "Default")
      (node (ref "J3") (pin "31") (pinfunction "31_31") (pintype "passive"))
    )
    (net (code "123") (name "unconnected-(J3-Pad33)") (class "Default")
      (node (ref "J3") (pin "33") (pinfunction "33_33") (pintype "passive"))
    )
    (net (code "124") (name "unconnected-(J3-Pad34)") (class "Default")
      (node (ref "J3") (pin "34") (pinfunction "34_34") (pintype "passive"))
    )
    (net (code "125") (name "unconnected-(J3-Pad42)") (class "Default")
      (node (ref "J3") (pin "42") (pinfunction "42_42") (pintype "passive"))
    )
    (net (code "126") (name "unconnected-(J3-Pad43)") (class "Default")
      (node (ref "J3") (pin "43") (pinfunction "43_43") (pintype "passive"))
    )
    (net (code "127") (name "unconnected-(J3-Pad45)") (class "Default")
      (node (ref "J3") (pin "45") (pinfunction "45_45") (pintype "passive"))
    )
    (net (code "128") (name "unconnected-(J3-Pad46)") (class "Default")
      (node (ref "J3") (pin "46") (pinfunction "46_46") (pintype "passive"))
    )
    (net (code "129") (name "unconnected-(J4-NC-Pad4)") (class "Default")
      (node (ref "J4") (pin "4") (pinfunction "NC_4") (pintype "passive"))
    )
    (net (code "130") (name "unconnected-(J4-NC-Pad5)") (class "Default")
      (node (ref "J4") (pin "5") (pinfunction "NC_5") (pintype "passive"))
    )
    (net (code "131") (name "unconnected-(J4-NC-Pad7)") (class "Default")
      (node (ref "J4") (pin "7") (pinfunction "NC_7") (pintype "passive"))
    )
    (net (code "132") (name "unconnected-(J4-NC-Pad8)") (class "Default")
      (node (ref "J4") (pin "8") (pinfunction "NC_8") (pintype "passive"))
    )
    (net (code "133") (name "unconnected-(LAN1-Pad2)") (class "Default")
      (node (ref "LAN1") (pin "2") (pintype "passive"))
    )
    (net (code "134") (name "unconnected-(LAN1-Pad5)") (class "Default")
      (node (ref "LAN1") (pin "5") (pintype "passive"))
    )
    (net (code "135") (name "unconnected-(LAN1-Pad8)") (class "Default")
      (node (ref "LAN1") (pin "8") (pintype "passive"))
    )
    (net (code "136") (name "unconnected-(LAN1-Pad11)") (class "Default")
      (node (ref "LAN1") (pin "11") (pintype "passive"))
    )
    (net (code "137") (name "unconnected-(LAN2-Pad2)") (class "Default")
      (node (ref "LAN2") (pin "2") (pintype "passive"))
    )
    (net (code "138") (name "unconnected-(LAN2-Pad5)") (class "Default")
      (node (ref "LAN2") (pin "5") (pintype "passive"))
    )
    (net (code "139") (name "unconnected-(LAN2-Pad8)") (class "Default")
      (node (ref "LAN2") (pin "8") (pintype "passive"))
    )
    (net (code "140") (name "unconnected-(LAN2-Pad11)") (class "Default")
      (node (ref "LAN2") (pin "11") (pintype "passive"))
    )
    (net (code "141") (name "unconnected-(LAN3-Pad2)") (class "Default")
      (node (ref "LAN3") (pin "2") (pintype "passive"))
    )
    (net (code "142") (name "unconnected-(LAN3-Pad5)") (class "Default")
      (node (ref "LAN3") (pin "5") (pintype "passive"))
    )
    (net (code "143") (name "unconnected-(LAN3-Pad8)") (class "Default")
      (node (ref "LAN3") (pin "8") (pintype "passive"))
    )
    (net (code "144") (name "unconnected-(LAN3-Pad11)") (class "Default")
      (node (ref "LAN3") (pin "11") (pintype "passive"))
    )
    (net (code "145") (name "unconnected-(LAN4-Pad2)") (class "Default")
      (node (ref "LAN4") (pin "2") (pintype "passive"))
    )
    (net (code "146") (name "unconnected-(LAN4-Pad5)") (class "Default")
      (node (ref "LAN4") (pin "5") (pintype "passive"))
    )
    (net (code "147") (name "unconnected-(LAN4-Pad8)") (class "Default")
      (node (ref "LAN4") (pin "8") (pintype "passive"))
    )
    (net (code "148") (name "unconnected-(LAN4-Pad11)") (class "Default")
      (node (ref "LAN4") (pin "11") (pintype "passive"))
    )
    (net (code "149") (name "unconnected-(WAN-Pad2)") (class "Default")
      (node (ref "WAN") (pin "2") (pintype "passive"))
    )
    (net (code "150") (name "unconnected-(WAN-Pad5)") (class "Default")
      (node (ref "WAN") (pin "5") (pintype "passive"))
    )
    (net (code "151") (name "unconnected-(WAN-Pad8)") (class "Default")
      (node (ref "WAN") (pin "8") (pintype "passive"))
    )
    (net (code "152") (name "unconnected-(WAN-Pad11)") (class "Default")
      (node (ref "WAN") (pin "11") (pintype "passive"))
    )
  )
)
